# led_driver.net
KiCad netlist of a schematic drawn in EAGLE
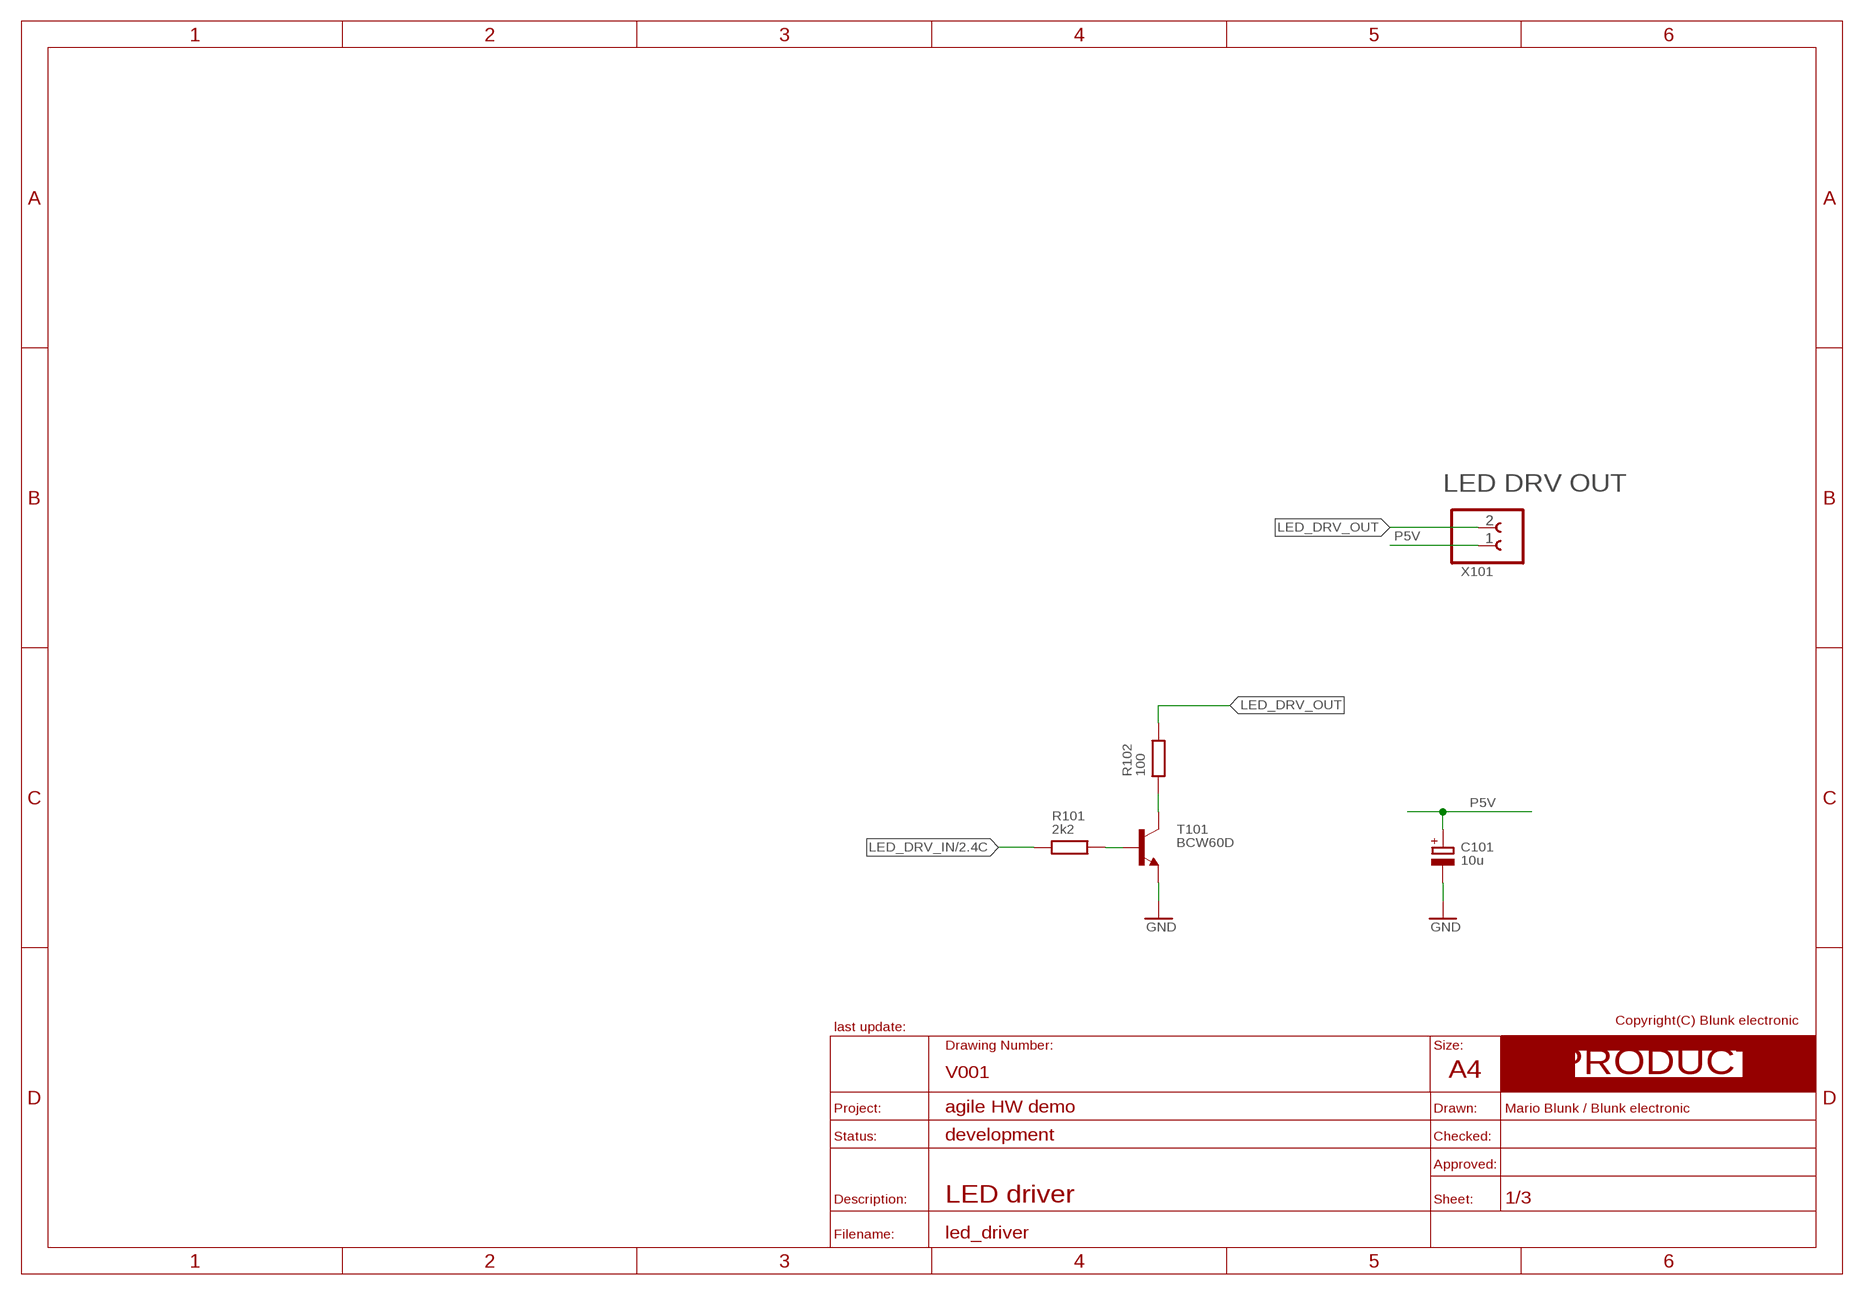
[diagram p0: schematic, sheet 1]
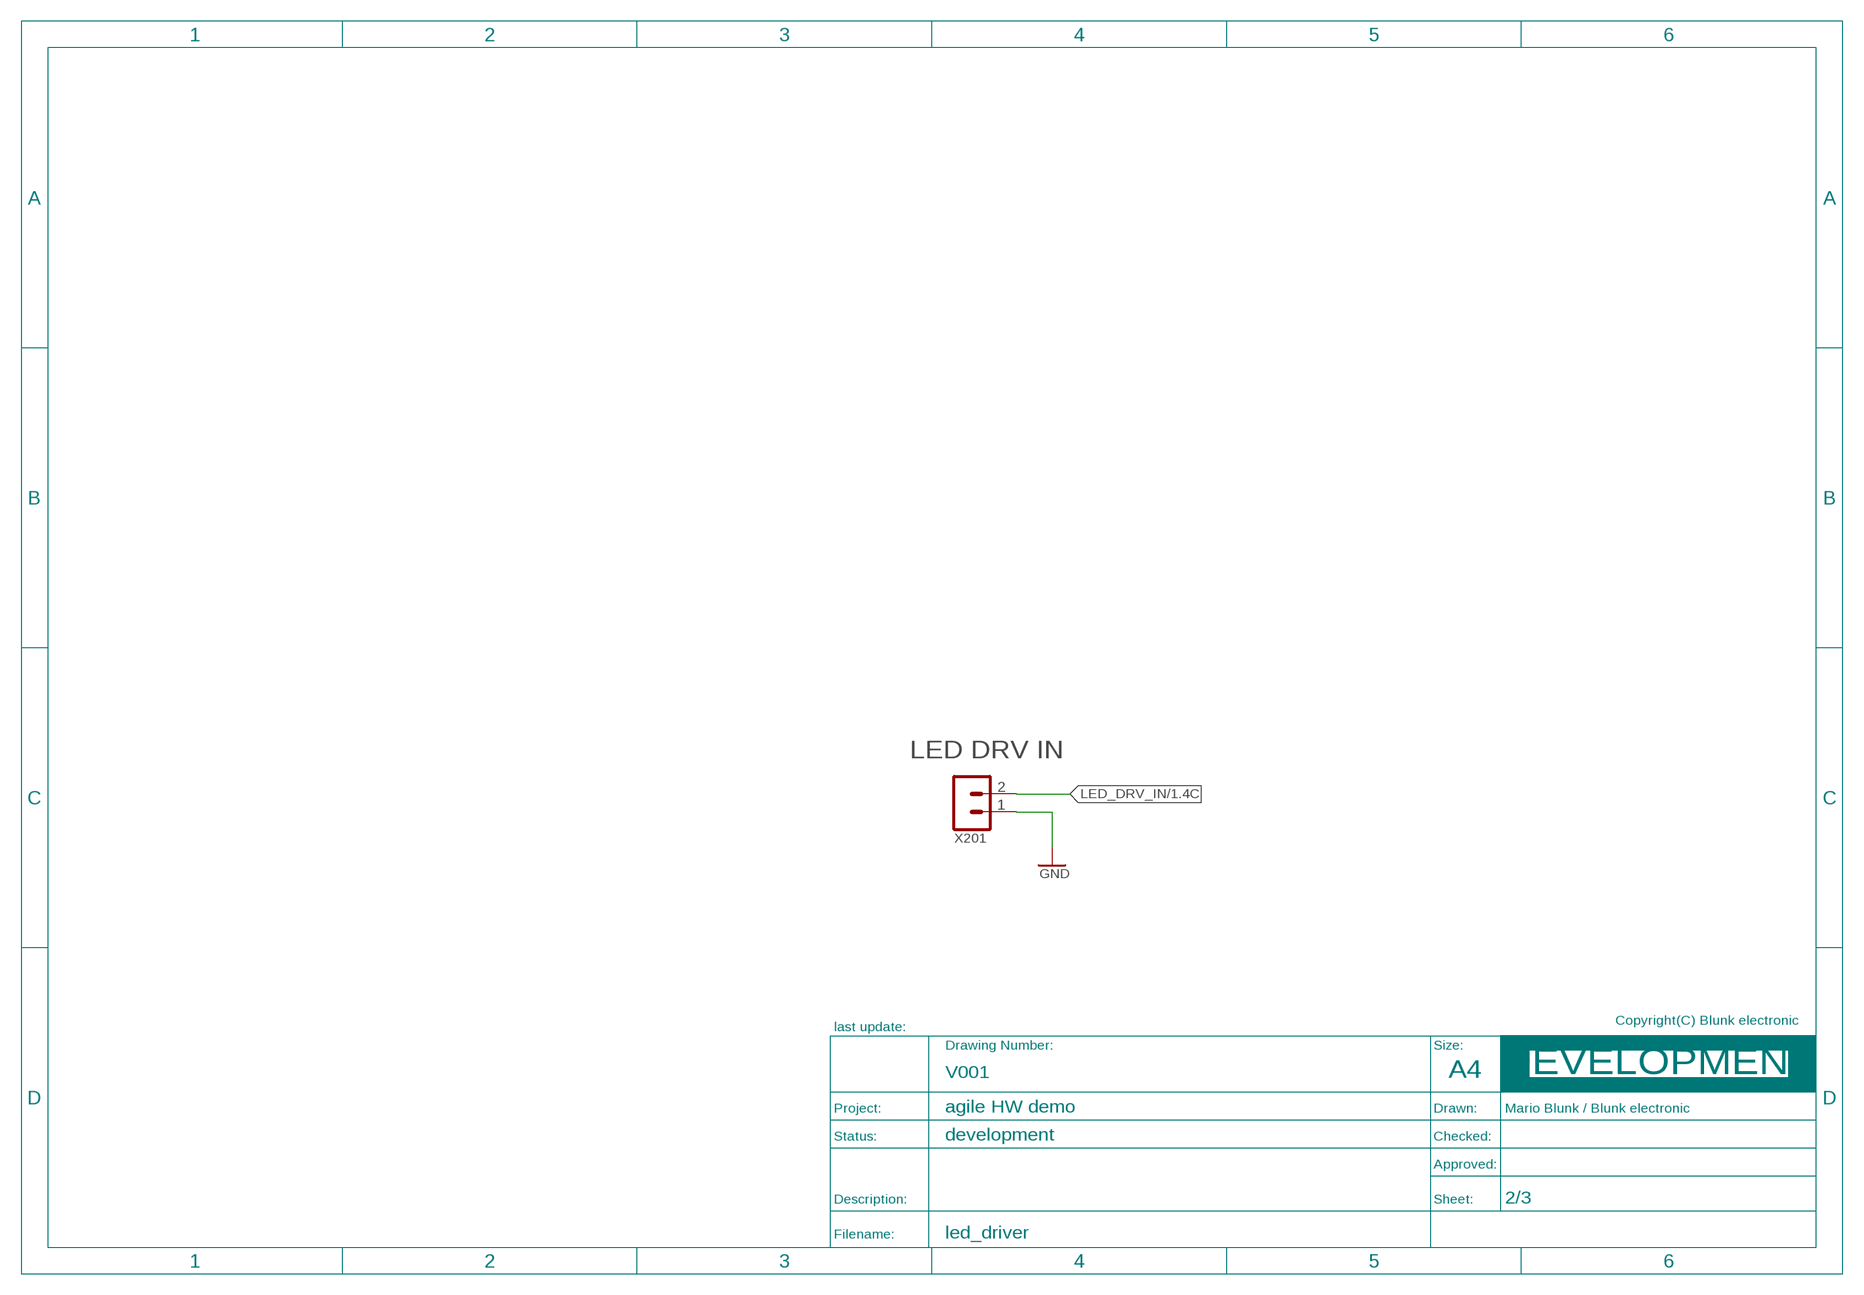
[diagram p1: schematic, sheet 2]
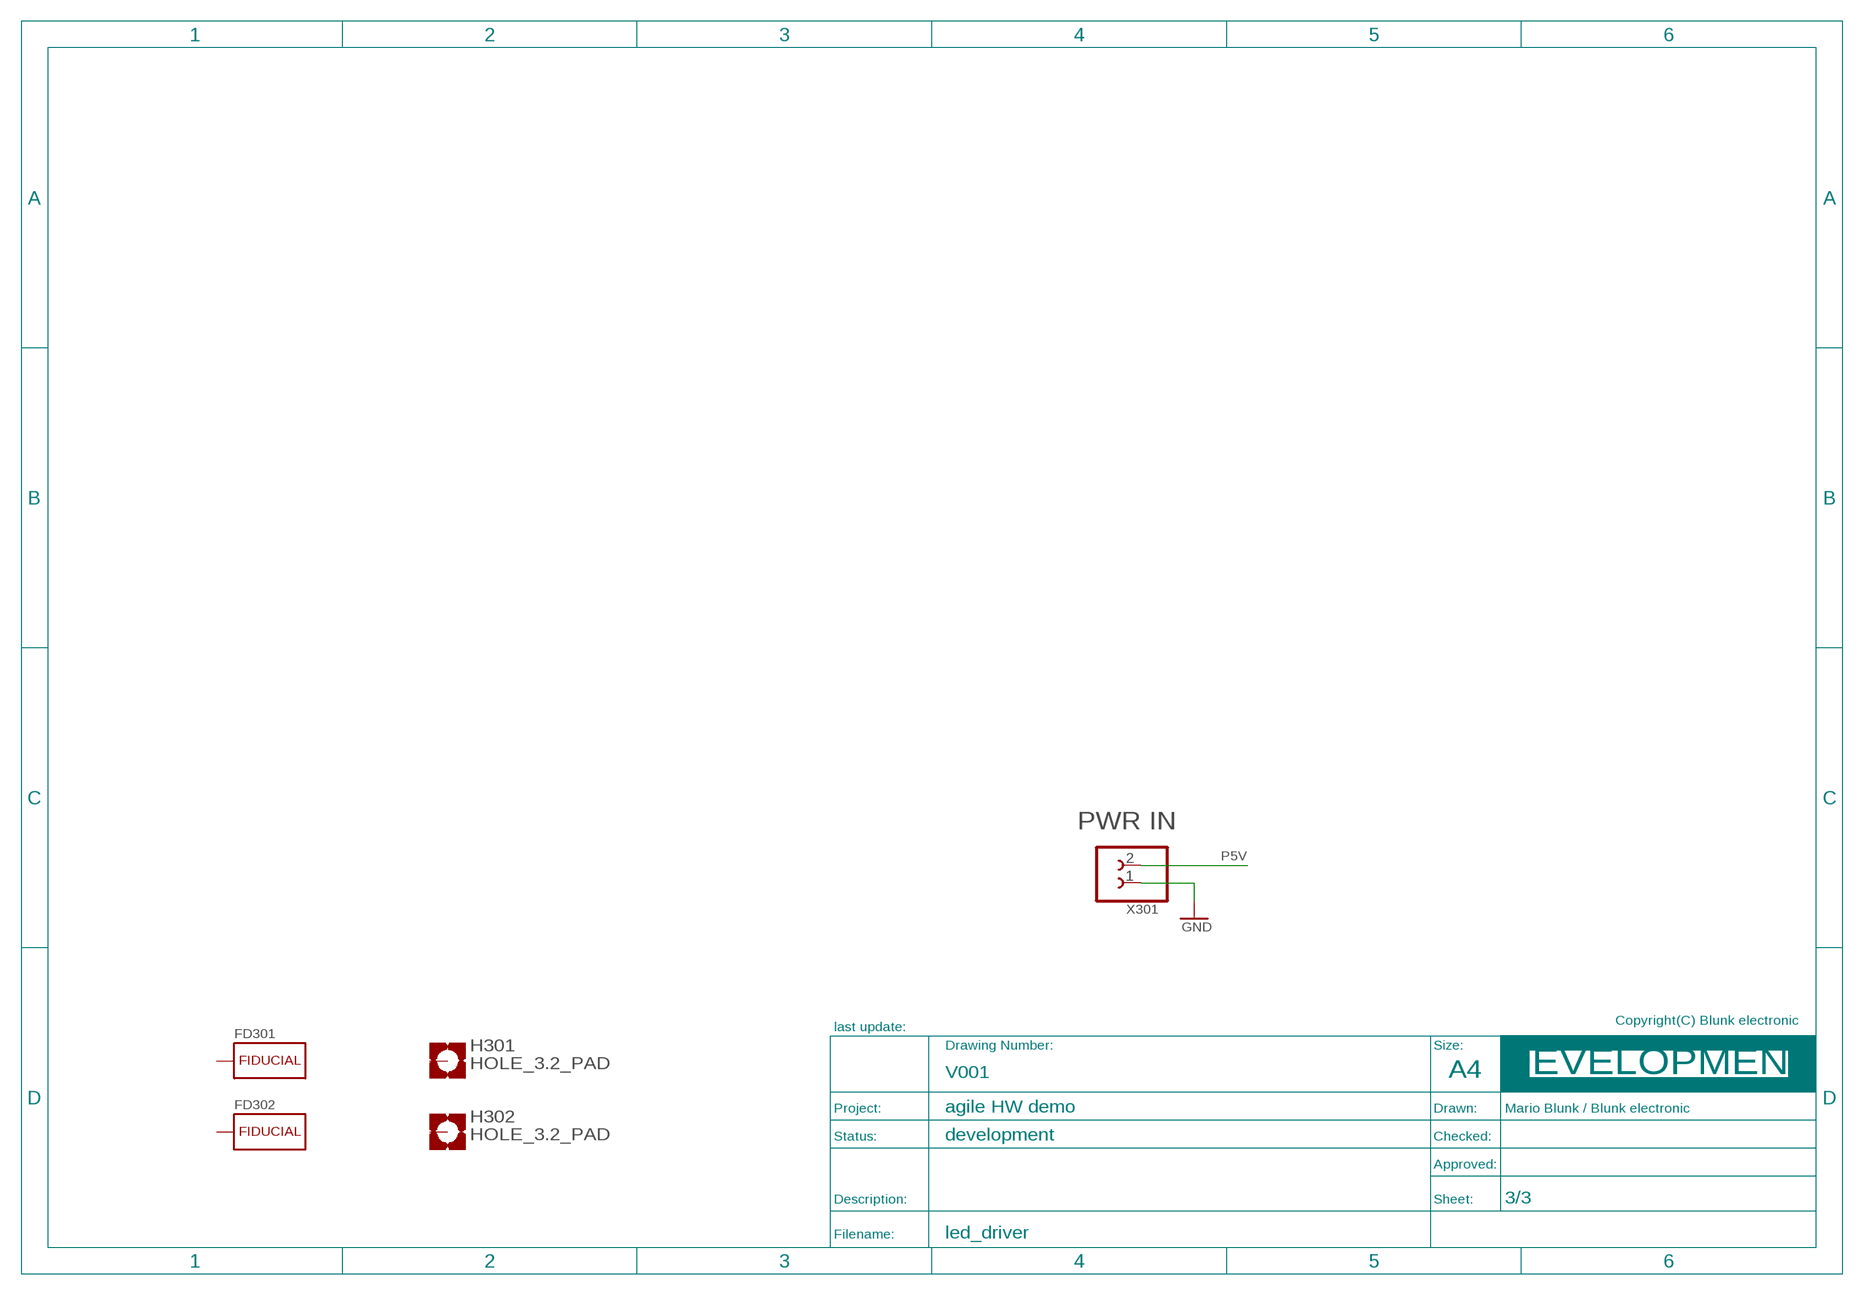
[diagram p2: schematic, sheet 3]

(export (version "E")
  (design (tool "Eeschema 10.0.6"))
  (components
    (comp (ref "C101")
      (value "10u")
      (footprint "eagle-import:S_6032")
      (fields (field (name "PART_CODE_BEL") "C_PAC_S_6032_VAL_10u_Vmax_35V"))
      (libsource (lib "eagle-import") (part "C_POL_S_6032"))
    )
    (comp (ref "R101")
      (value "2k2")
      (footprint "eagle-import:S_0805")
      (fields (field (name "PART_CODE_BEL") "R_PAC_S_0805_VAL_2k2"))
      (libsource (lib "eagle-import") (part "R_S_0805"))
    )
    (comp (ref "R102")
      (value "100")
      (footprint "eagle-import:S_0805")
      (fields (field (name "PART_CODE_BEL") "R_PAC_S_0805_VAL_100"))
      (libsource (lib "eagle-import") (part "R_S_0805"))
    )
    (comp (ref "T101")
      (value "BCW60D")
      (footprint "eagle-import:S_SOT23")
      (fields (field (name "PART_CODE_BEL") "T_PAC_S_SOT23_VAL_BCW60D"))
      (libsource (lib "eagle-import") (part "NPN_S_SOT23"))
    )
    (comp (ref "X101")
      (value "CLAMP_1X2-T-2.5MM")
      (footprint "eagle-import:T_WIRE_CLAMP_1X2_PITCH_2MM5")
      (fields (field (name "FUNCTION") "LED DRV OUT"))
      (libsource (lib "eagle-import") (part "CLAMP_1X2-T-2.5MM"))
    )
    (comp (ref "X201")
      (value "MALE_2X1-T-VERTICAL")
      (footprint "eagle-import:T_MALE_2X1_VERTICAL_PITCH_2MM54")
      (fields (field (name "FUNCTION") "LED DRV IN"))
      (libsource (lib "eagle-import") (part "MALE_2X1-T-VERTICAL"))
    )
    (comp (ref "FD301")
      (value "FIDUCIAL_CROSSHAIR")
      (footprint "eagle-import:CROSSHAIR")
      (libsource (lib "eagle-import") (part "FIDUCIAL_CROSSHAIR"))
    )
    (comp (ref "FD302")
      (value "FIDUCIAL_CROSSHAIR")
      (footprint "eagle-import:CROSSHAIR")
      (libsource (lib "eagle-import") (part "FIDUCIAL_CROSSHAIR"))
    )
    (comp (ref "H301")
      (value "HOLE_3.2_PAD")
      (footprint "eagle-import:3.2_PAD")
      (libsource (lib "eagle-import") (part "HOLE_3.2_PAD"))
    )
    (comp (ref "H302")
      (value "HOLE_3.2_PAD")
      (footprint "eagle-import:3.2_PAD")
      (libsource (lib "eagle-import") (part "HOLE_3.2_PAD"))
    )
    (comp (ref "X301")
      (value "CLAMP_1X2-T-2.5MM")
      (footprint "eagle-import:T_WIRE_CLAMP_1X2_PITCH_2MM5")
      (fields (field (name "FUNCTION") "PWR IN"))
      (libsource (lib "eagle-import") (part "CLAMP_1X2-T-2.5MM"))
    )
  )
  (nets
    (net (code "1") (name "GND") (class "Default")
      (node (ref "C101") (pin "-") (pinfunction "-_-") (pintype "passive"))
      (node (ref "T101") (pin "2") (pinfunction "E_2") (pintype "passive"))
      (node (ref "X201") (pin "1") (pinfunction "1_1") (pintype "passive"))
      (node (ref "X301") (pin "1") (pinfunction "1_1") (pintype "passive"))
    )
    (net (code "2") (name "LED_DRV_IN") (class "Default")
      (node (ref "R101") (pin "1") (pinfunction "1_1") (pintype "passive"))
      (node (ref "X201") (pin "2") (pinfunction "2_2") (pintype "passive"))
    )
    (net (code "3") (name "LED_DRV_OUT") (class "Default")
      (node (ref "R102") (pin "2") (pinfunction "2_2") (pintype "passive"))
      (node (ref "X101") (pin "2") (pinfunction "2_2") (pintype "passive"))
    )
    (net (code "4") (name "Net-(T101-B)") (class "Default")
      (node (ref "R101") (pin "2") (pinfunction "2_2") (pintype "passive"))
      (node (ref "T101") (pin "1") (pinfunction "B_1") (pintype "passive"))
    )
    (net (code "5") (name "Net-(T101-C)") (class "Default")
      (node (ref "R102") (pin "1") (pinfunction "1_1") (pintype "passive"))
      (node (ref "T101") (pin "3") (pinfunction "C_3") (pintype "passive"))
    )
    (net (code "6") (name "P5V") (class "Default")
      (node (ref "C101") (pin "+") (pinfunction "+_+") (pintype "passive"))
      (node (ref "X101") (pin "1") (pinfunction "1_1") (pintype "passive"))
      (node (ref "X301") (pin "2") (pinfunction "2_2") (pintype "passive"))
    )
    (net (code "7") (name "unconnected-(FD301-NC-Pad1)") (class "Default")
      (node (ref "FD301") (pin "1") (pinfunction "NC_1") (pintype "no_connect"))
    )
    (net (code "8") (name "unconnected-(FD302-NC-Pad1)") (class "Default")
      (node (ref "FD302") (pin "1") (pinfunction "NC_1") (pintype "no_connect"))
    )
    (net (code "9") (name "unconnected-(H301-MOUNT-PadH1)") (class "Default")
      (node (ref "H301") (pin "H1") (pinfunction "MOUNT_H1") (pintype "passive"))
    )
    (net (code "10") (name "unconnected-(H302-MOUNT-PadH1)") (class "Default")
      (node (ref "H302") (pin "H1") (pinfunction "MOUNT_H1") (pintype "passive"))
    )
  )
)
